# BT40_v23.net
KiCad netlist of a schematic drawn in EAGLE
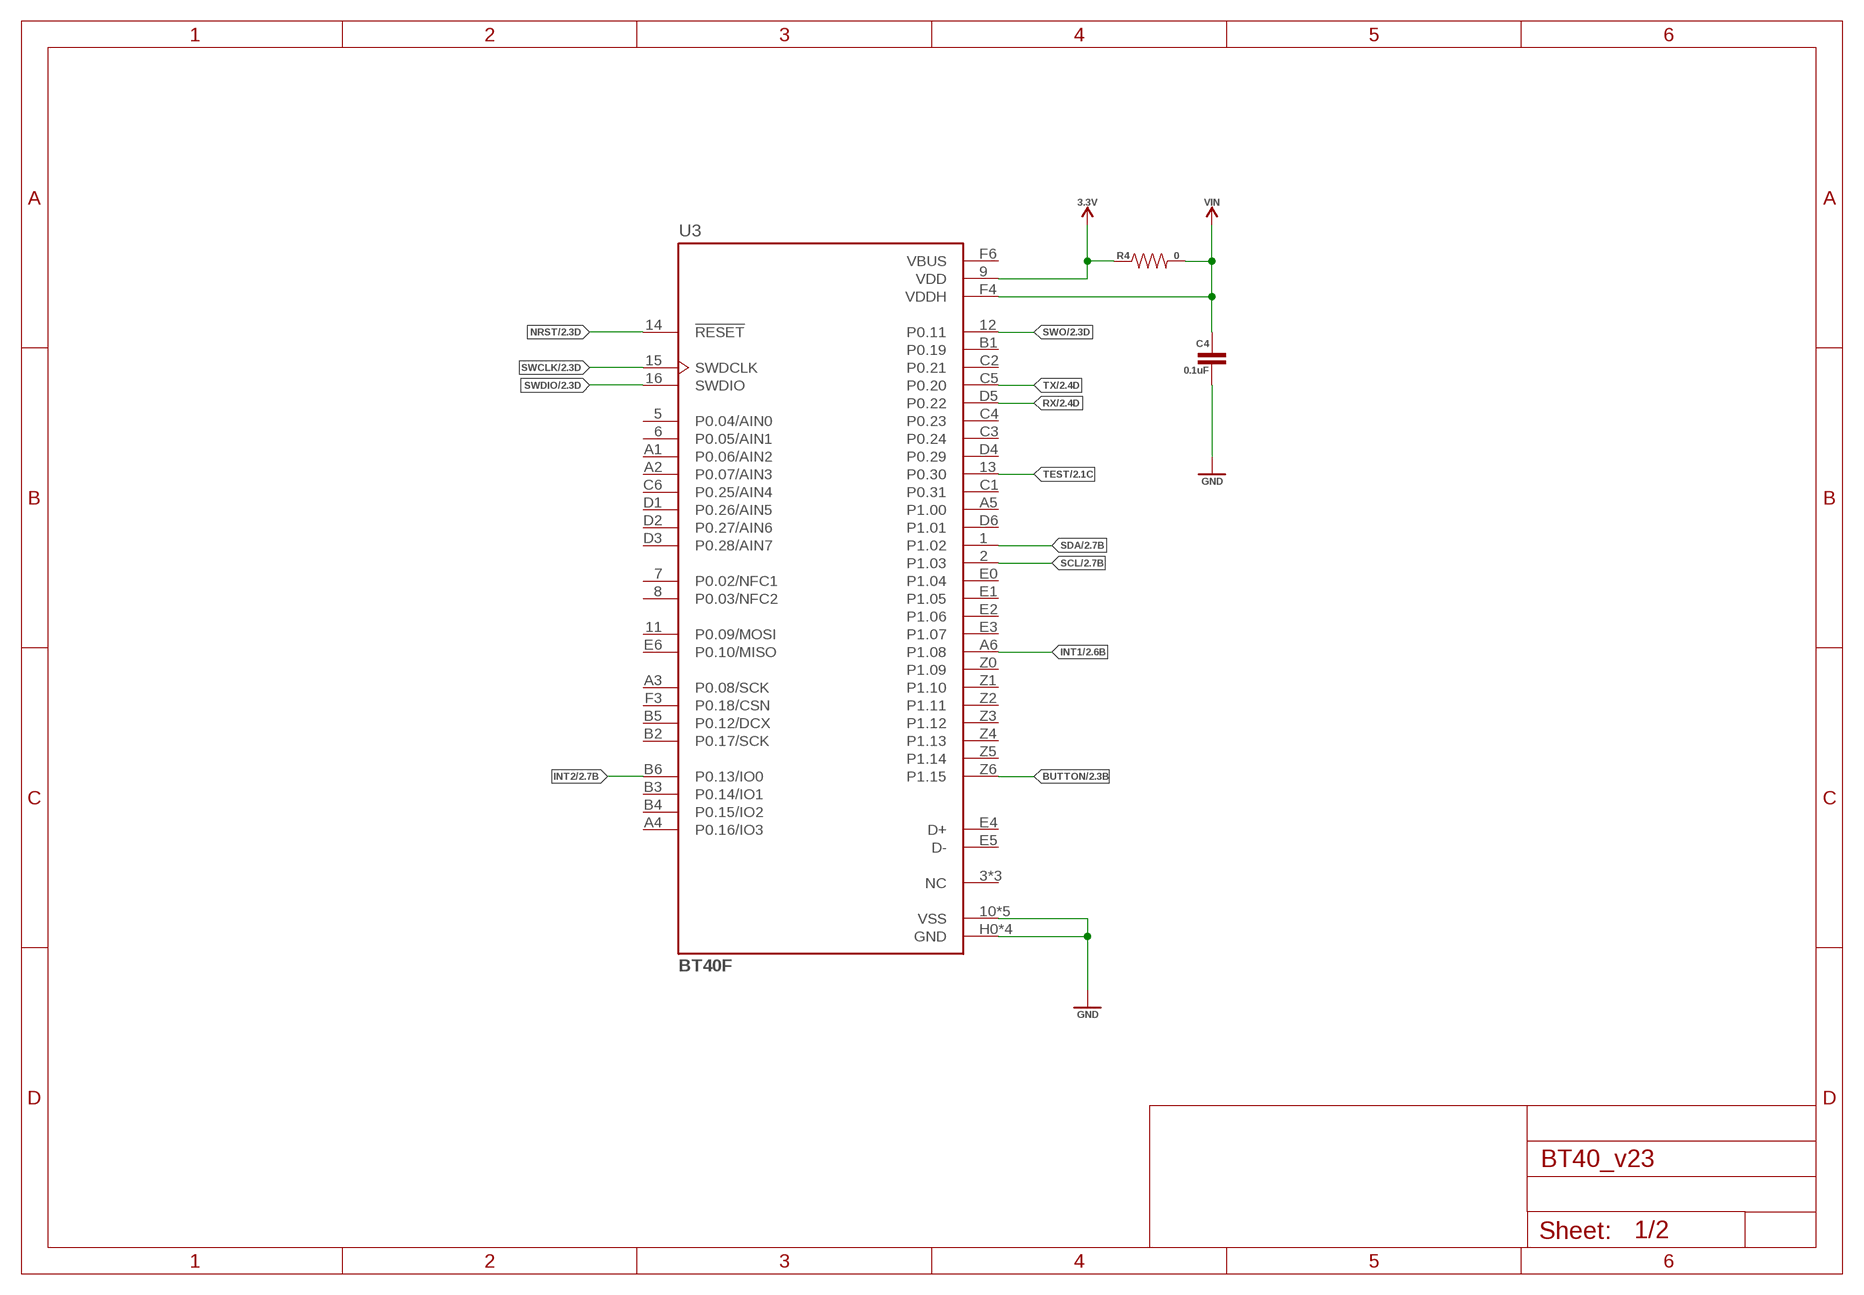
[diagram p0: schematic, sheet 1]
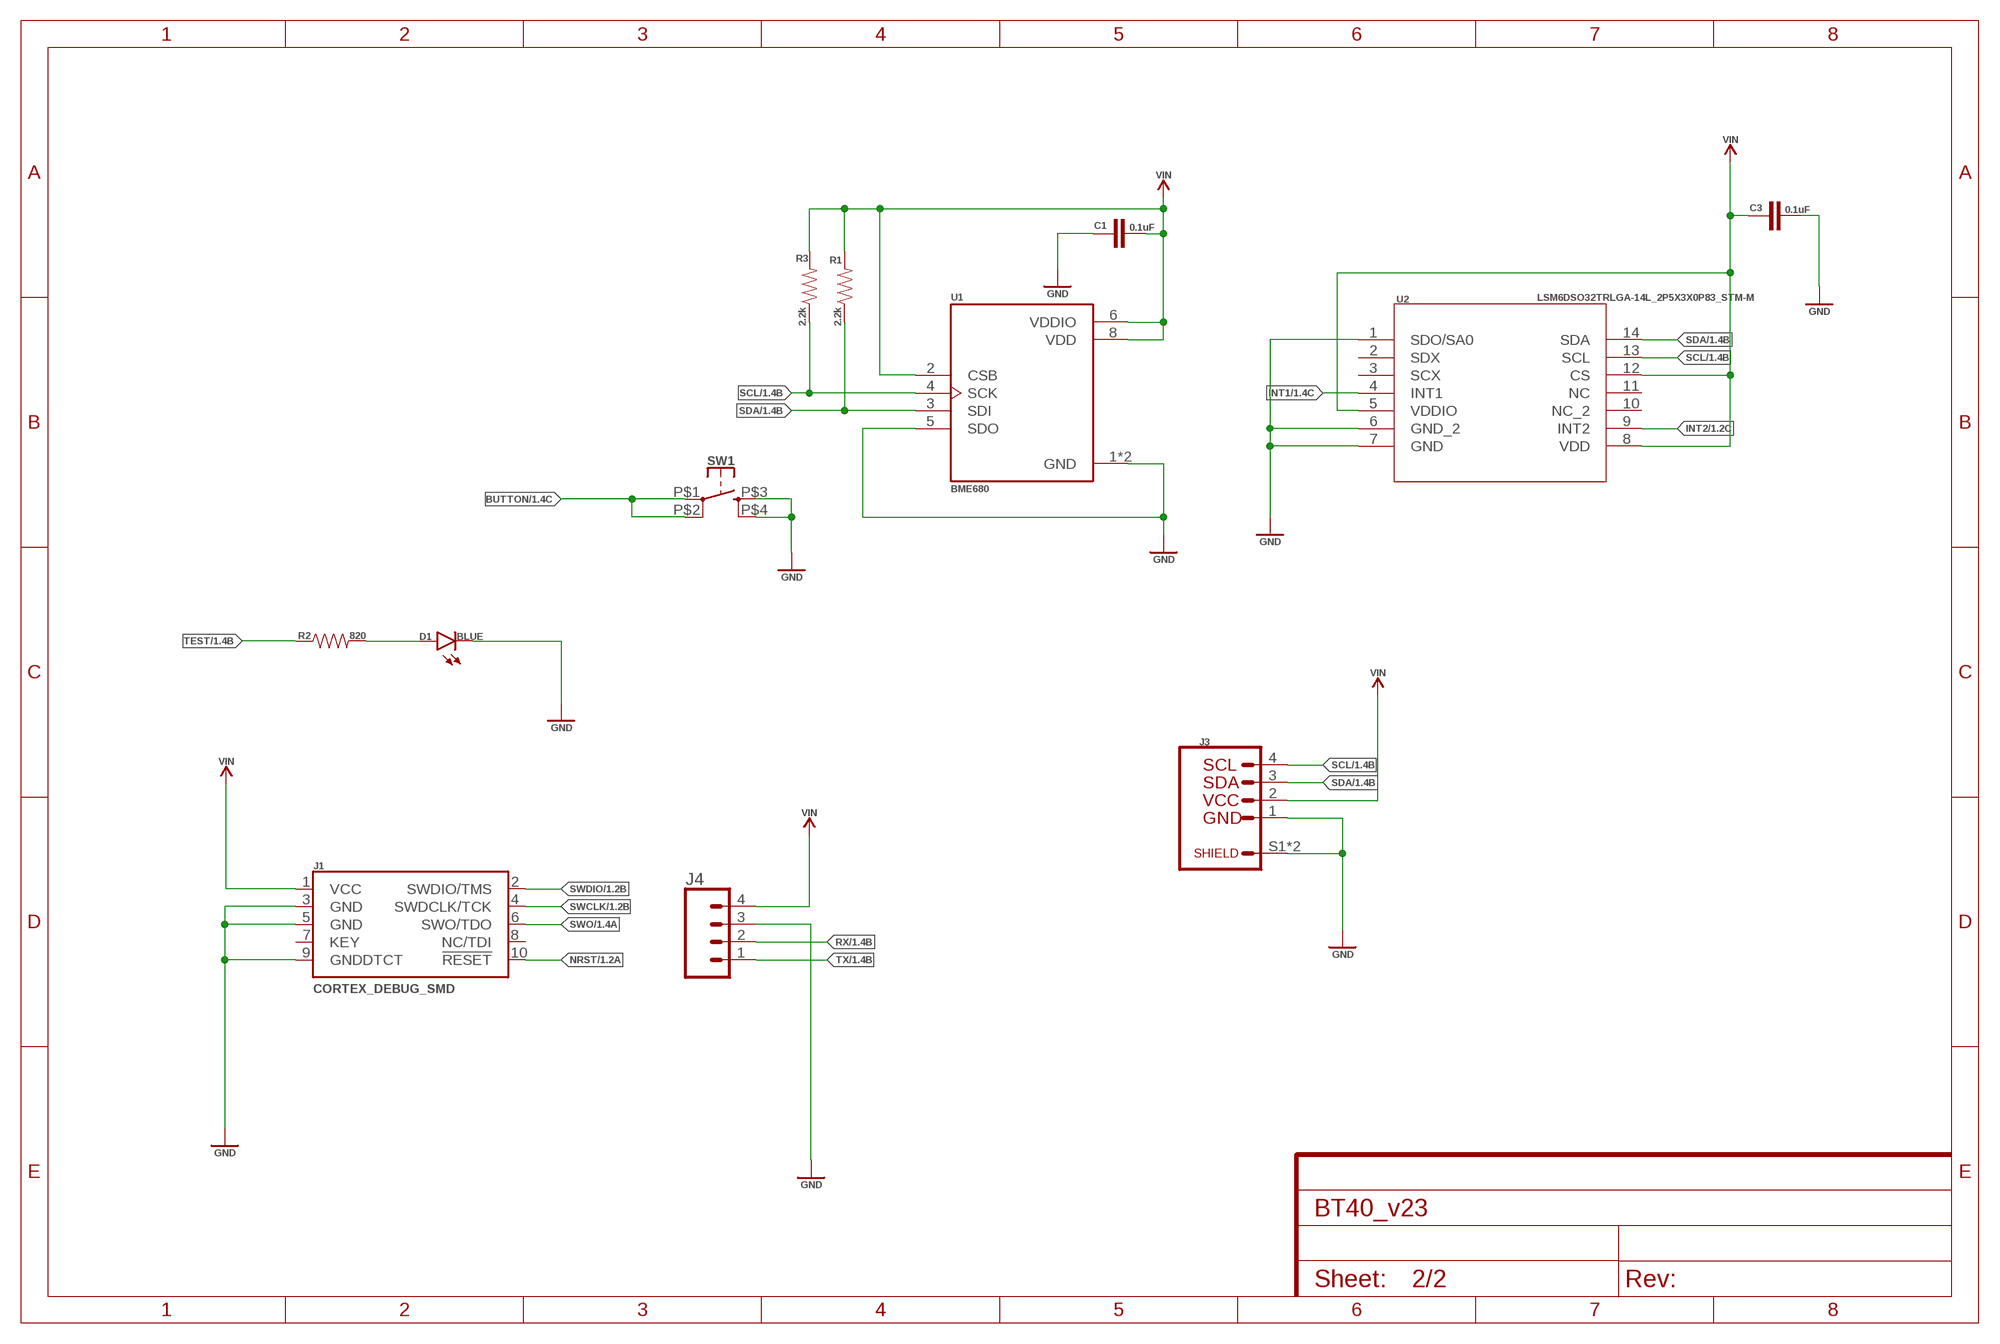
[diagram p1: schematic, sheet 2]

(export (version "E")
  (design (tool "Eeschema 10.0.6"))
  (components
    (comp (ref "C1")
      (value "0.1uF")
      (footprint "eagle-import:0603")
      (libsource (lib "eagle-import") (part "0.1UF-0603-25V-(+80/-20%)"))
    )
    (comp (ref "C3")
      (value "0.1uF")
      (footprint "eagle-import:0603")
      (libsource (lib "eagle-import") (part "0.1UF-0603-25V-(+80/-20%)"))
    )
    (comp (ref "D1")
      (value "BLUE")
      (footprint "eagle-import:LED-0603")
      (libsource (lib "eagle-import") (part "LED-BLUE0603"))
    )
    (comp (ref "J1")
      (value "CORTEX_DEBUG_SMD")
      (footprint "eagle-import:SAMTECH_FTSH-105-01")
      (libsource (lib "eagle-import") (part "CORTEX_DEBUG_SMD"))
    )
    (comp (ref "J3")
      (value "QWIIC")
      (footprint "eagle-import:CONN_BM04B-SRSS-TB(LF)(SN)")
      (libsource (lib "eagle-import") (part "QWIIC"))
    )
    (comp (ref "J4")
      (value "CONN_04SMD")
      (footprint "eagle-import:1X04_SMD_RA_MALE")
      (libsource (lib "eagle-import") (part "CONN_04SMD"))
    )
    (comp (ref "R1")
      (value "2.2k")
      (footprint "eagle-import:0603")
      (libsource (lib "eagle-import") (part "2.2KOHM-0603-1/10W-1%"))
    )
    (comp (ref "R2")
      (value "820")
      (footprint "eagle-import:0603")
      (fields (field (name "SPICEPREFIX") "R"))
      (libsource (lib "eagle-import") (part "8.2KOHM-0603-1/10W-5%"))
    )
    (comp (ref "R3")
      (value "2.2k")
      (footprint "eagle-import:0603")
      (libsource (lib "eagle-import") (part "2.2KOHM-0603-1/10W-1%"))
    )
    (comp (ref "SW1")
      (value "REVERSE_SWITCH")
      (footprint "eagle-import:REVERSE_TACTILE")
      (libsource (lib "eagle-import") (part "REVERSE_SWITCH"))
    )
    (comp (ref "U1")
      (value "BME680")
      (footprint "eagle-import:PSON80P300X300X100-8N")
      (fields (field (name "MF") "Bosch Sensortec"))
      (libsource (lib "eagle-import") (part "BME680"))
    )
    (comp (ref "U2")
      (value "LSM6DSO32TRLGA-14L_2P5X3X0P83_STM-M")
      (footprint "eagle-import:LGA-14L_2P5X3X0P83_STM-M")
      (fields
        (field (name "MANUFACTURER_PART_NUMBER") "LSM6DSO32TR")
        (field (name "COPYRIGHT") "Copyright (C) 2022 Ultra Librarian. All rights reserved.")
      )
      (libsource (lib "eagle-import") (part "LSM6DSO32TRLGA-14L_2P5X3X0P83_STM-M"))
    )
    (comp (ref "C4")
      (value "0.1uF")
      (footprint "eagle-import:0603")
      (libsource (lib "eagle-import") (part "0.1UF-0603-25V-(+80/-20%)"))
    )
    (comp (ref "R4")
      (value "0")
      (footprint "eagle-import:0603")
      (libsource (lib "eagle-import") (part "0OHM-0603-1/10W-5%"))
    )
    (comp (ref "U3")
      (value "BT40F")
      (footprint "eagle-import:XCVR_BT40F")
      (fields (field (name "MF") "Fanstel Corp."))
      (libsource (lib "eagle-import") (part "BT40F"))
    )
  )
  (nets
    (net (code "1") (name "3.3V") (class "Default")
      (node (ref "R4") (pin "1") (pinfunction "1_1") (pintype "passive"))
      (node (ref "U3") (pin "9") (pinfunction "VDD_9") (pintype "power_in"))
    )
    (net (code "2") (name "BUTTON") (class "Default")
      (node (ref "SW1") (pin "P$1") (pinfunction "1_P$1") (pintype "passive"))
      (node (ref "SW1") (pin "P$2") (pinfunction "2_P$2") (pintype "passive"))
      (node (ref "U3") (pin "Z6") (pinfunction "P1.15_Z6") (pintype "bidirectional"))
    )
    (net (code "3") (name "GND") (class "Default")
      (node (ref "C1") (pin "1") (pinfunction "1_1") (pintype "passive"))
      (node (ref "C3") (pin "2") (pinfunction "2_2") (pintype "passive"))
      (node (ref "C4") (pin "2") (pinfunction "2_2") (pintype "passive"))
      (node (ref "D1") (pin "C") (pinfunction "C_C") (pintype "passive"))
      (node (ref "J1") (pin "3") (pinfunction "GND_3") (pintype "bidirectional"))
      (node (ref "J1") (pin "5") (pinfunction "GND_5") (pintype "bidirectional"))
      (node (ref "J1") (pin "9") (pinfunction "GNDDTCT_9") (pintype "bidirectional"))
      (node (ref "J3") (pin "1") (pinfunction "1_1") (pintype "power_in"))
      (node (ref "J3") (pin "S1") (pinfunction "P$2_S1") (pintype "power_in"))
      (node (ref "J3") (pin "S2") (pinfunction "P$2_S2") (pintype "power_in"))
      (node (ref "J4") (pin "3") (pinfunction "SDA_3") (pintype "passive"))
      (node (ref "SW1") (pin "P$3") (pinfunction "3_P$3") (pintype "passive"))
      (node (ref "SW1") (pin "P$4") (pinfunction "4_P$4") (pintype "passive"))
      (node (ref "U1") (pin "1") (pinfunction "GND_1") (pintype "power_in"))
      (node (ref "U1") (pin "5") (pinfunction "SDO_5") (pintype "bidirectional"))
      (node (ref "U1") (pin "7") (pinfunction "GND_7") (pintype "power_in"))
      (node (ref "U2") (pin "1") (pinfunction "SDO/SA0_1") (pintype "bidirectional"))
      (node (ref "U2") (pin "6") (pinfunction "GND_2_6") (pintype "passive"))
      (node (ref "U2") (pin "7") (pinfunction "GND_7") (pintype "passive"))
      (node (ref "U3") (pin "10") (pinfunction "VSS_10") (pintype "power_in"))
      (node (ref "U3") (pin "A0") (pinfunction "VSS_A0") (pintype "power_in"))
      (node (ref "U3") (pin "B0") (pinfunction "VSS_B0") (pintype "power_in"))
      (node (ref "U3") (pin "C0") (pinfunction "VSS_C0") (pintype "power_in"))
      (node (ref "U3") (pin "D0") (pinfunction "VSS_D0") (pintype "power_in"))
      (node (ref "U3") (pin "H0") (pinfunction "GND_H0") (pintype "power_in"))
      (node (ref "U3") (pin "H1") (pinfunction "GND_H1") (pintype "power_in"))
      (node (ref "U3") (pin "H2") (pinfunction "GND_H2") (pintype "power_in"))
      (node (ref "U3") (pin "H3") (pinfunction "GND_H3") (pintype "power_in"))
    )
    (net (code "4") (name "INT1") (class "Default")
      (node (ref "U2") (pin "4") (pinfunction "INT1_4") (pintype "output"))
      (node (ref "U3") (pin "A6") (pinfunction "P1.08_A6") (pintype "bidirectional"))
    )
    (net (code "5") (name "INT2") (class "Default")
      (node (ref "U2") (pin "9") (pinfunction "INT2_9") (pintype "output"))
      (node (ref "U3") (pin "B6") (pinfunction "P0.13/IO0_B6") (pintype "bidirectional"))
    )
    (net (code "6") (name "NRST") (class "Default")
      (node (ref "J1") (pin "10") (pinfunction "~{RESET}_10") (pintype "bidirectional"))
      (node (ref "U3") (pin "14") (pinfunction "~{RESET}_14") (pintype "input"))
    )
    (net (code "7") (name "Net-(D1-PadA)") (class "Default")
      (node (ref "D1") (pin "A") (pinfunction "A_A") (pintype "passive"))
      (node (ref "R2") (pin "2") (pinfunction "2_2") (pintype "passive"))
    )
    (net (code "8") (name "RX") (class "Default")
      (node (ref "J4") (pin "2") (pinfunction "SCL_2") (pintype "passive"))
      (node (ref "U3") (pin "D5") (pinfunction "P0.22_D5") (pintype "bidirectional"))
    )
    (net (code "9") (name "SCL") (class "Default")
      (node (ref "J3") (pin "4") (pinfunction "4_4") (pintype "passive"))
      (node (ref "R3") (pin "1") (pinfunction "1_1") (pintype "passive"))
      (node (ref "U1") (pin "4") (pinfunction "SCK_4") (pintype "input"))
      (node (ref "U2") (pin "13") (pinfunction "SCL_13") (pintype "input"))
      (node (ref "U3") (pin "2") (pinfunction "P1.03_2") (pintype "bidirectional"))
    )
    (net (code "10") (name "SDA") (class "Default")
      (node (ref "J3") (pin "3") (pinfunction "3_3") (pintype "passive"))
      (node (ref "R1") (pin "1") (pinfunction "1_1") (pintype "passive"))
      (node (ref "U1") (pin "3") (pinfunction "SDI_3") (pintype "bidirectional"))
      (node (ref "U2") (pin "14") (pinfunction "SDA_14") (pintype "bidirectional"))
      (node (ref "U3") (pin "1") (pinfunction "P1.02_1") (pintype "bidirectional"))
    )
    (net (code "11") (name "SWCLK") (class "Default")
      (node (ref "J1") (pin "4") (pinfunction "SWDCLK/TCK_4") (pintype "bidirectional"))
      (node (ref "U3") (pin "15") (pinfunction "SWDCLK_15") (pintype "input"))
    )
    (net (code "12") (name "SWDIO") (class "Default")
      (node (ref "J1") (pin "2") (pinfunction "SWDIO/TMS_2") (pintype "bidirectional"))
      (node (ref "U3") (pin "16") (pinfunction "SWDIO_16") (pintype "bidirectional"))
    )
    (net (code "13") (name "SWO") (class "Default")
      (node (ref "J1") (pin "6") (pinfunction "SWO/TDO_6") (pintype "bidirectional"))
      (node (ref "U3") (pin "12") (pinfunction "P0.11_12") (pintype "bidirectional"))
    )
    (net (code "14") (name "TEST") (class "Default")
      (node (ref "R2") (pin "1") (pinfunction "1_1") (pintype "passive"))
      (node (ref "U3") (pin "13") (pinfunction "P0.30_13") (pintype "bidirectional"))
    )
    (net (code "15") (name "TX") (class "Default")
      (node (ref "J4") (pin "1") (pinfunction "VCC_1") (pintype "passive"))
      (node (ref "U3") (pin "C5") (pinfunction "P0.20_C5") (pintype "bidirectional"))
    )
    (net (code "16") (name "VBUS") (class "Default")
      (node (ref "U3") (pin "F6") (pinfunction "VBUS_F6") (pintype "power_in"))
    )
    (net (code "17") (name "VIN") (class "Default")
      (node (ref "C1") (pin "2") (pinfunction "2_2") (pintype "passive"))
      (node (ref "C3") (pin "1") (pinfunction "1_1") (pintype "passive"))
      (node (ref "C4") (pin "1") (pinfunction "1_1") (pintype "passive"))
      (node (ref "J1") (pin "1") (pinfunction "VCC_1") (pintype "bidirectional"))
      (node (ref "J3") (pin "2") (pinfunction "2_2") (pintype "power_in"))
      (node (ref "J4") (pin "4") (pinfunction "GND_4") (pintype "passive"))
      (node (ref "R1") (pin "2") (pinfunction "2_2") (pintype "passive"))
      (node (ref "R3") (pin "2") (pinfunction "2_2") (pintype "passive"))
      (node (ref "R4") (pin "2") (pinfunction "2_2") (pintype "passive"))
      (node (ref "U1") (pin "2") (pinfunction "CSB_2") (pintype "input"))
      (node (ref "U1") (pin "6") (pinfunction "VDDIO_6") (pintype "power_in"))
      (node (ref "U1") (pin "8") (pinfunction "VDD_8") (pintype "power_in"))
      (node (ref "U2") (pin "12") (pinfunction "CS_12") (pintype "input"))
      (node (ref "U2") (pin "5") (pinfunction "VDDIO_5") (pintype "power_in"))
      (node (ref "U2") (pin "8") (pinfunction "VDD_8") (pintype "power_in"))
      (node (ref "U3") (pin "F4") (pinfunction "VDDH_F4") (pintype "power_in"))
    )
    (net (code "18") (name "unconnected-(J1-KEY-Pad7)") (class "Default")
      (node (ref "J1") (pin "7") (pinfunction "KEY_7") (pintype "bidirectional"))
    )
    (net (code "19") (name "unconnected-(J1-NC{slash}TDI-Pad8)") (class "Default")
      (node (ref "J1") (pin "8") (pinfunction "NC/TDI_8") (pintype "bidirectional"))
    )
    (net (code "20") (name "unconnected-(U2-NC-Pad11)") (class "Default")
      (node (ref "U2") (pin "11") (pinfunction "NC_11") (pintype "no_connect"))
    )
    (net (code "21") (name "unconnected-(U2-NC_2-Pad10)") (class "Default")
      (node (ref "U2") (pin "10") (pinfunction "NC_2_10") (pintype "no_connect"))
    )
    (net (code "22") (name "unconnected-(U2-SCX-Pad3)") (class "Default")
      (node (ref "U2") (pin "3") (pinfunction "SCX_3") (pintype "passive"))
    )
    (net (code "23") (name "unconnected-(U2-SDX-Pad2)") (class "Default")
      (node (ref "U2") (pin "2") (pinfunction "SDX_2") (pintype "passive"))
    )
    (net (code "24") (name "unconnected-(U3-D+-PadE4)") (class "Default")
      (node (ref "U3") (pin "E4") (pinfunction "D+_E4") (pintype "bidirectional"))
    )
    (net (code "25") (name "unconnected-(U3-D--PadE5)") (class "Default")
      (node (ref "U3") (pin "E5") (pinfunction "D-_E5") (pintype "bidirectional"))
    )
    (net (code "26") (name "unconnected-(U3-NC-Pad3)") (class "Default")
      (node (ref "U3") (pin "3") (pinfunction "NC_3") (pintype "no_connect"))
    )
    (net (code "27") (name "unconnected-(U3-NC-Pad4)") (class "Default")
      (node (ref "U3") (pin "4") (pinfunction "NC_4") (pintype "no_connect"))
    )
    (net (code "28") (name "unconnected-(U3-NC-PadF5)") (class "Default")
      (node (ref "U3") (pin "F5") (pinfunction "NC_F5") (pintype "no_connect"))
    )
    (net (code "29") (name "unconnected-(U3-P0.02{slash}NFC1-Pad7)") (class "Default")
      (node (ref "U3") (pin "7") (pinfunction "P0.02/NFC1_7") (pintype "bidirectional"))
    )
    (net (code "30") (name "unconnected-(U3-P0.03{slash}NFC2-Pad8)") (class "Default")
      (node (ref "U3") (pin "8") (pinfunction "P0.03/NFC2_8") (pintype "bidirectional"))
    )
    (net (code "31") (name "unconnected-(U3-P0.04{slash}AIN0-Pad5)") (class "Default")
      (node (ref "U3") (pin "5") (pinfunction "P0.04/AIN0_5") (pintype "bidirectional"))
    )
    (net (code "32") (name "unconnected-(U3-P0.05{slash}AIN1-Pad6)") (class "Default")
      (node (ref "U3") (pin "6") (pinfunction "P0.05/AIN1_6") (pintype "bidirectional"))
    )
    (net (code "33") (name "unconnected-(U3-P0.06{slash}AIN2-PadA1)") (class "Default")
      (node (ref "U3") (pin "A1") (pinfunction "P0.06/AIN2_A1") (pintype "bidirectional"))
    )
    (net (code "34") (name "unconnected-(U3-P0.07{slash}AIN3-PadA2)") (class "Default")
      (node (ref "U3") (pin "A2") (pinfunction "P0.07/AIN3_A2") (pintype "bidirectional"))
    )
    (net (code "35") (name "unconnected-(U3-P0.08{slash}SCK-PadA3)") (class "Default")
      (node (ref "U3") (pin "A3") (pinfunction "P0.08/SCK_A3") (pintype "bidirectional"))
    )
    (net (code "36") (name "unconnected-(U3-P0.09{slash}MOSI-Pad11)") (class "Default")
      (node (ref "U3") (pin "11") (pinfunction "P0.09/MOSI_11") (pintype "bidirectional"))
    )
    (net (code "37") (name "unconnected-(U3-P0.10{slash}MISO-PadE6)") (class "Default")
      (node (ref "U3") (pin "E6") (pinfunction "P0.10/MISO_E6") (pintype "bidirectional"))
    )
    (net (code "38") (name "unconnected-(U3-P0.12{slash}DCX-PadB5)") (class "Default")
      (node (ref "U3") (pin "B5") (pinfunction "P0.12/DCX_B5") (pintype "bidirectional"))
    )
    (net (code "39") (name "unconnected-(U3-P0.14{slash}IO1-PadB3)") (class "Default")
      (node (ref "U3") (pin "B3") (pinfunction "P0.14/IO1_B3") (pintype "bidirectional"))
    )
    (net (code "40") (name "unconnected-(U3-P0.15{slash}IO2-PadB4)") (class "Default")
      (node (ref "U3") (pin "B4") (pinfunction "P0.15/IO2_B4") (pintype "bidirectional"))
    )
    (net (code "41") (name "unconnected-(U3-P0.16{slash}IO3-PadA4)") (class "Default")
      (node (ref "U3") (pin "A4") (pinfunction "P0.16/IO3_A4") (pintype "bidirectional"))
    )
    (net (code "42") (name "unconnected-(U3-P0.17{slash}SCK-PadB2)") (class "Default")
      (node (ref "U3") (pin "B2") (pinfunction "P0.17/SCK_B2") (pintype "bidirectional"))
    )
    (net (code "43") (name "unconnected-(U3-P0.18{slash}CSN-PadF3)") (class "Default")
      (node (ref "U3") (pin "F3") (pinfunction "P0.18/CSN_F3") (pintype "bidirectional"))
    )
    (net (code "44") (name "unconnected-(U3-P0.19-PadB1)") (class "Default")
      (node (ref "U3") (pin "B1") (pinfunction "P0.19_B1") (pintype "bidirectional"))
    )
    (net (code "45") (name "unconnected-(U3-P0.21-PadC2)") (class "Default")
      (node (ref "U3") (pin "C2") (pinfunction "P0.21_C2") (pintype "bidirectional"))
    )
    (net (code "46") (name "unconnected-(U3-P0.23-PadC4)") (class "Default")
      (node (ref "U3") (pin "C4") (pinfunction "P0.23_C4") (pintype "bidirectional"))
    )
    (net (code "47") (name "unconnected-(U3-P0.24-PadC3)") (class "Default")
      (node (ref "U3") (pin "C3") (pinfunction "P0.24_C3") (pintype "bidirectional"))
    )
    (net (code "48") (name "unconnected-(U3-P0.25{slash}AIN4-PadC6)") (class "Default")
      (node (ref "U3") (pin "C6") (pinfunction "P0.25/AIN4_C6") (pintype "bidirectional"))
    )
    (net (code "49") (name "unconnected-(U3-P0.26{slash}AIN5-PadD1)") (class "Default")
      (node (ref "U3") (pin "D1") (pinfunction "P0.26/AIN5_D1") (pintype "bidirectional"))
    )
    (net (code "50") (name "unconnected-(U3-P0.27{slash}AIN6-PadD2)") (class "Default")
      (node (ref "U3") (pin "D2") (pinfunction "P0.27/AIN6_D2") (pintype "bidirectional"))
    )
    (net (code "51") (name "unconnected-(U3-P0.28{slash}AIN7-PadD3)") (class "Default")
      (node (ref "U3") (pin "D3") (pinfunction "P0.28/AIN7_D3") (pintype "bidirectional"))
    )
    (net (code "52") (name "unconnected-(U3-P0.29-PadD4)") (class "Default")
      (node (ref "U3") (pin "D4") (pinfunction "P0.29_D4") (pintype "bidirectional"))
    )
    (net (code "53") (name "unconnected-(U3-P0.31-PadC1)") (class "Default")
      (node (ref "U3") (pin "C1") (pinfunction "P0.31_C1") (pintype "bidirectional"))
    )
    (net (code "54") (name "unconnected-(U3-P1.00-PadA5)") (class "Default")
      (node (ref "U3") (pin "A5") (pinfunction "P1.00_A5") (pintype "bidirectional"))
    )
    (net (code "55") (name "unconnected-(U3-P1.01-PadD6)") (class "Default")
      (node (ref "U3") (pin "D6") (pinfunction "P1.01_D6") (pintype "bidirectional"))
    )
    (net (code "56") (name "unconnected-(U3-P1.04-PadE0)") (class "Default")
      (node (ref "U3") (pin "E0") (pinfunction "P1.04_E0") (pintype "bidirectional"))
    )
    (net (code "57") (name "unconnected-(U3-P1.05-PadE1)") (class "Default")
      (node (ref "U3") (pin "E1") (pinfunction "P1.05_E1") (pintype "bidirectional"))
    )
    (net (code "58") (name "unconnected-(U3-P1.06-PadE2)") (class "Default")
      (node (ref "U3") (pin "E2") (pinfunction "P1.06_E2") (pintype "bidirectional"))
    )
    (net (code "59") (name "unconnected-(U3-P1.07-PadE3)") (class "Default")
      (node (ref "U3") (pin "E3") (pinfunction "P1.07_E3") (pintype "bidirectional"))
    )
    (net (code "60") (name "unconnected-(U3-P1.09-PadZ0)") (class "Default")
      (node (ref "U3") (pin "Z0") (pinfunction "P1.09_Z0") (pintype "bidirectional"))
    )
    (net (code "61") (name "unconnected-(U3-P1.10-PadZ1)") (class "Default")
      (node (ref "U3") (pin "Z1") (pinfunction "P1.10_Z1") (pintype "bidirectional"))
    )
    (net (code "62") (name "unconnected-(U3-P1.11-PadZ2)") (class "Default")
      (node (ref "U3") (pin "Z2") (pinfunction "P1.11_Z2") (pintype "bidirectional"))
    )
    (net (code "63") (name "unconnected-(U3-P1.12-PadZ3)") (class "Default")
      (node (ref "U3") (pin "Z3") (pinfunction "P1.12_Z3") (pintype "bidirectional"))
    )
    (net (code "64") (name "unconnected-(U3-P1.13-PadZ4)") (class "Default")
      (node (ref "U3") (pin "Z4") (pinfunction "P1.13_Z4") (pintype "bidirectional"))
    )
    (net (code "65") (name "unconnected-(U3-P1.14-PadZ5)") (class "Default")
      (node (ref "U3") (pin "Z5") (pinfunction "P1.14_Z5") (pintype "bidirectional"))
    )
  )
)
